# MAIN.net
KiCad netlist of a schematic drawn in Altium Designer
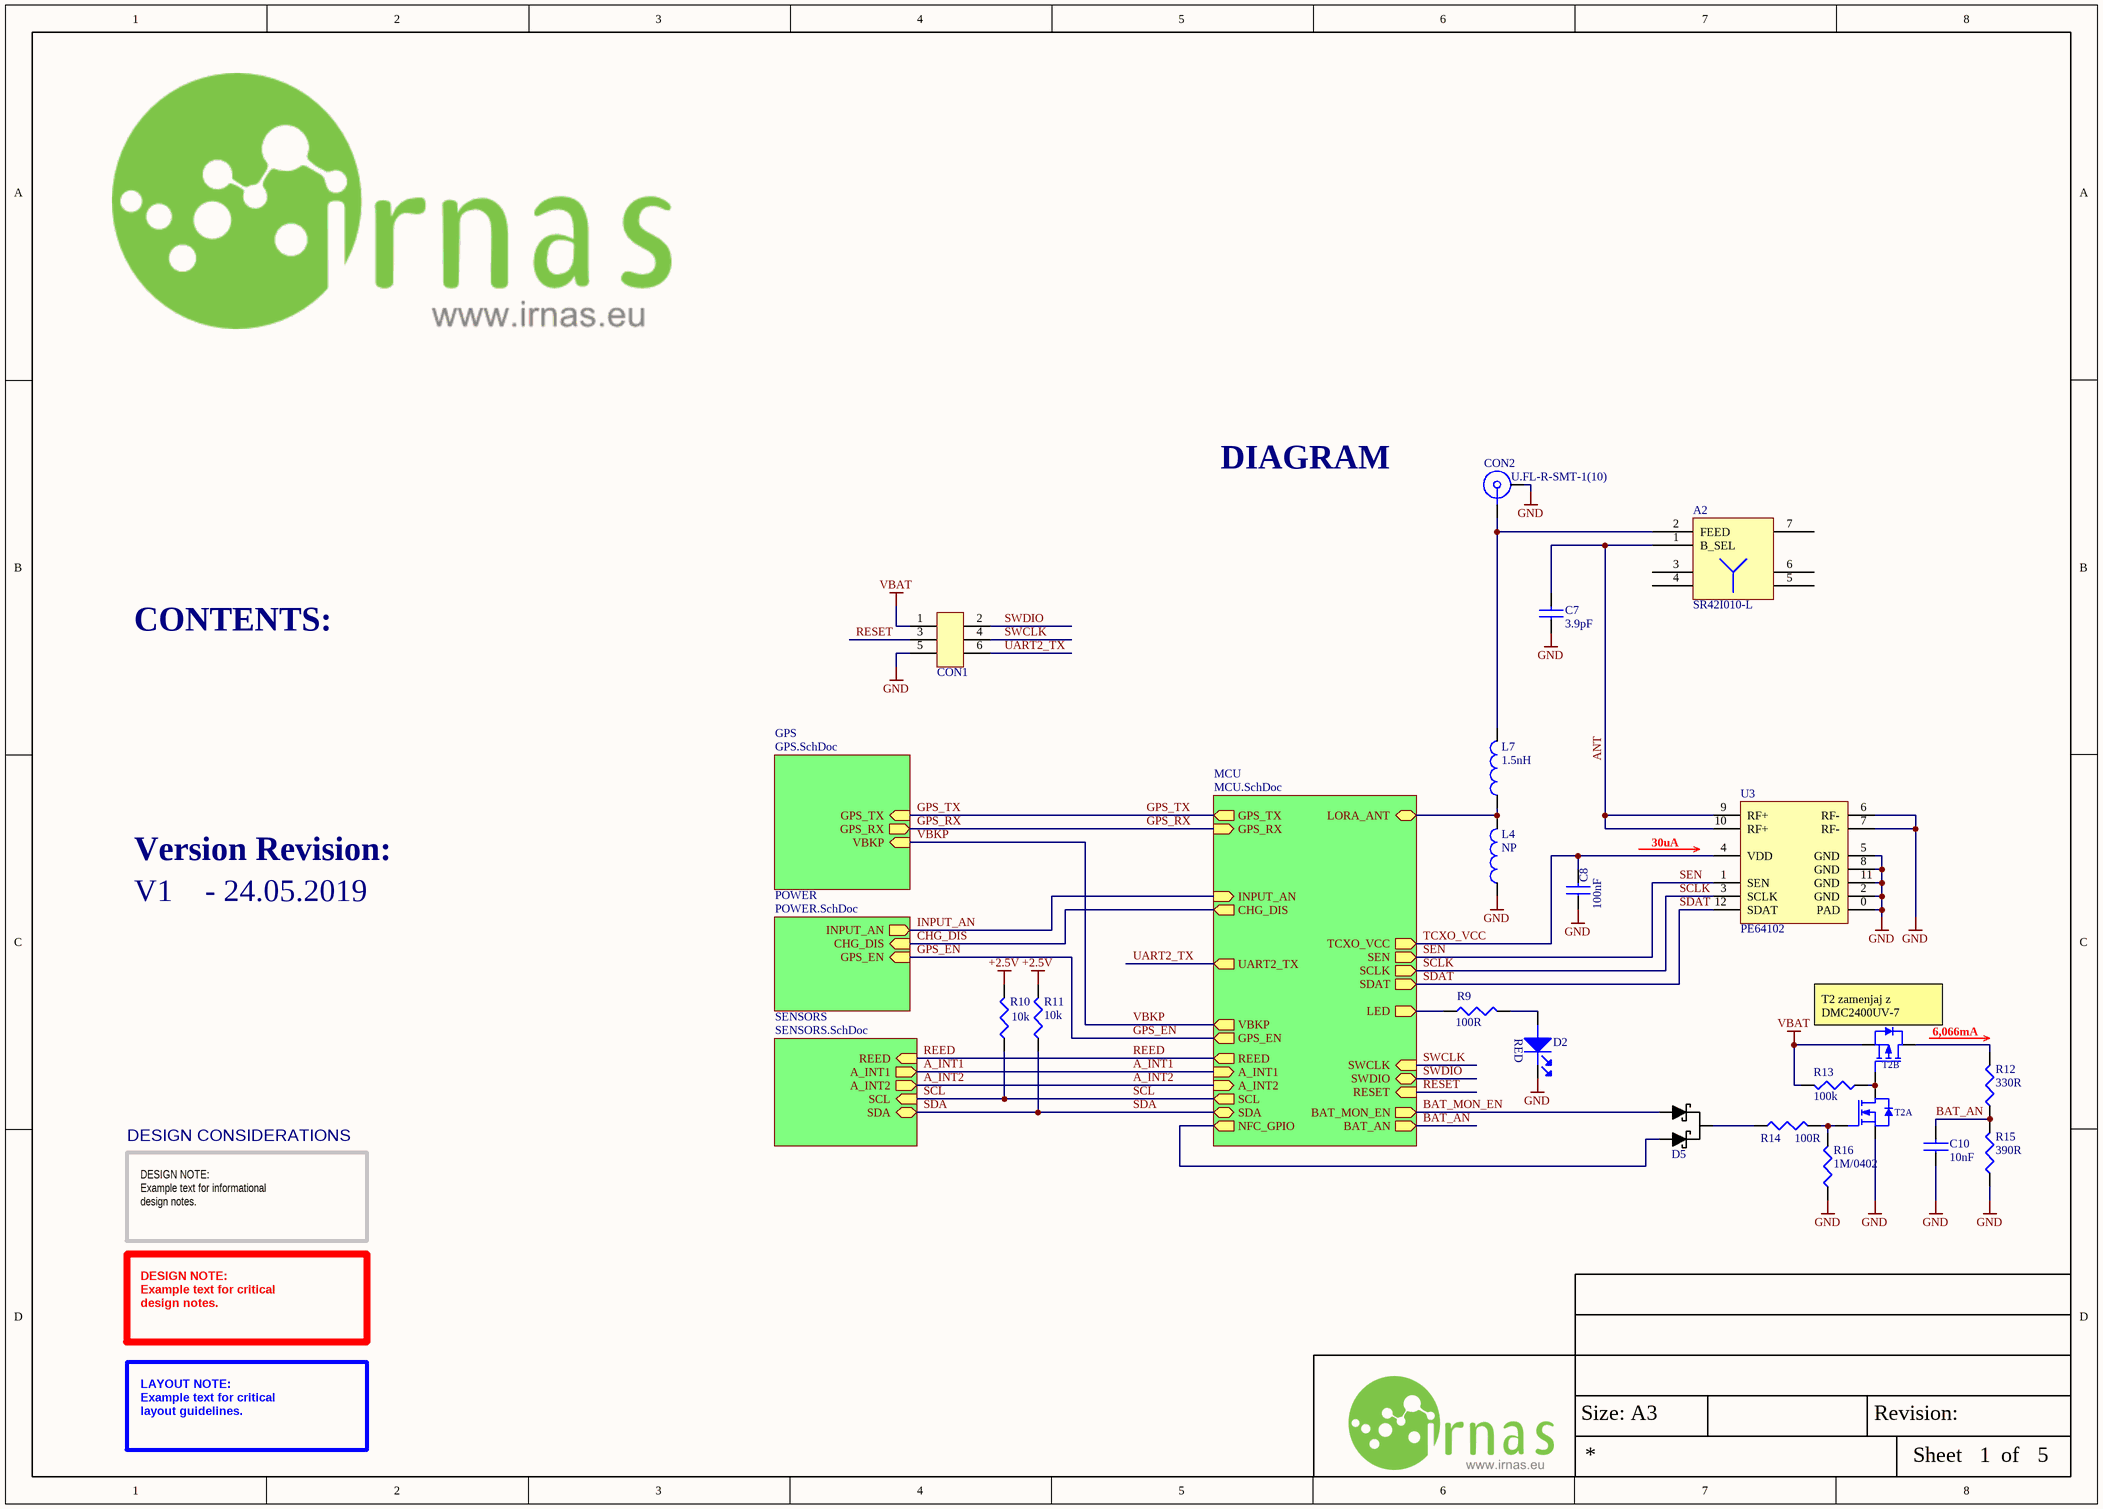
[diagram p0: MAIN.SchDoc]

(export (version "E")
  (design (tool "Eeschema 10.0.6"))
  (components
    (comp (ref "A2")
      (value "SR42I010-L")
      (footprint "SR42I010-L")
      (description "Antenna SMD -4dBi Gain 870MHz/928MHz Automotive 7-Pin SMD T/R")
      (fields (field (name "MANUFACTURER") "Antenova") (field (name "MANUFACTURER PART NUMBER") "SR42I010-R"))
      (libsource (lib "Passive") (part "ANT - SR42I010-L"))
    )
    (comp (ref "C7")
      (value "3.9pF")
      (footprint "CAP0402")
      (description "3.9 pF, 50 V, 0402 [1005 Metric], ± 0.25pF, NP0")
      (fields
        (field (name "MANUFACTURER") "KEMET")
        (field (name "MANUFACTURER PART NUMBER") "MC0402N3R9C500CT")
      )
      (libsource (lib "Passive") (part "C - 3.9pF/0402"))
    )
    (comp (ref "C8")
      (value "100nF")
      (footprint "CAP0402")
      (description "0.1 F, 16 V,  5%, X5R, MC Series")
      (fields
        (field (name "MANUFACTURER") "Multicomp")
        (field (name "MANUFACTURER PART NUMBER") "MC0402X104J160CT")
      )
      (libsource (lib "Passive") (part "C - 100nF/0402"))
    )
    (comp (ref "C10")
      (value "10nF")
      (footprint "CAP0402")
      (description "CAP CER 10000PF 16V X7R 0402")
      (fields
        (field (name "MANUFACTURER") "Murata")
        (field (name "MANUFACTURER PART NUMBER") "GRM155R71C103KA01D")
      )
      (libsource (lib "Passive") (part "C - 10nF/0402"))
    )
    (comp (ref "CON1")
      (value "Tag connect")
      (footprint "TC2030-IDC-NL")
      (libsource (lib "Connectors") (part "tag connecot 6 pin"))
    )
    (comp (ref "CON2")
      (value "U.FL-R-SMT-1(10)")
      (footprint "ufl connector smd")
      (description "RF / Coaxial Connector, U.FL Coaxial, Straight Jack, Surface Mount Vertical, 50 ohm, Brass")
      (fields (field (name "MANUFACTURER") "Hirose"))
      (libsource (lib "Connectors") (part "U.FL-R-SMT-1(10)"))
    )
    (comp (ref "D2")
      (value "LED RED")
      (footprint "LED0603")
      (description "BROADCOM LIMITED - HSMS-C190 - LED, RED, 10MCD, 626NM")
      (fields
        (field (name "MANUFACTURER") "BROADCOM LIMITED")
        (field (name "MANUFACTURER PART NUMBER") "HSMS-C190")
      )
      (libsource (lib "Active") (part "LED - LED RED"))
    )
    (comp (ref "D5")
      (value "BAS70-05,215")
      (footprint "SOT 23")
      (description "Small Signal Schottky Diode, Dual Common Cathode, 70 V, 70 mA, 410 mV, 100 mA, 150 °C")
      (libsource (lib "Active") (part "DS - BAS40-05"))
    )
    (comp (ref "L4")
      (value "NP")
      (footprint "IND0402")
      (description "Inductor RF Chip Multi-Layer 4.3nH 0.3nH 100MHz 8Q-Factor Air 300mA 210mOhm DCR 0402 Paper T/R")
      (fields
        (field (name "MANUFACTURER") "Murata")
        (field (name "MANUFACTURER PART NUMBER") "LQG15HN4N3S02D")
      )
      (libsource (lib "Passive") (part "L - 4.3nH/0402"))
    )
    (comp (ref "L7")
      (value "1.5nH")
      (footprint "IND0402")
      (description "1.5 nH, LQG15HS_02 Series, 1 A, 0402")
      (fields
        (field (name "MANUFACTURER") "Murata")
        (field (name "MANUFACTURER PART NUMBER") "LQG15HS1N5S02D")
      )
      (libsource (lib "Passive") (part "L - 1.5nH/0402"))
    )
    (comp (ref "R9")
      (value "100R")
      (footprint "RES0402")
      (description "100 ohm, 50 V, 0402 [1005 Metric], 62.5 mW,  1%")
      (fields
        (field (name "MANUFACTURER") "Multicomp")
        (field (name "MANUFACTURER PART NUMBER") "MCMR04X1000FTL")
      )
      (libsource (lib "Passive") (part "R - 100R/0402"))
    )
    (comp (ref "R10")
      (value "10k")
      (footprint "RES0402")
      (description "10 kohm, 50 V, 0402 [1005 Metric], 62.5 mW,  1%, MCWR Series")
      (fields
        (field (name "MANUFACTURER") "Multicomp")
        (field (name "MANUFACTURER PART NUMBER") "MCWR04X1002FTL")
      )
      (libsource (lib "Passive") (part "R - 10k/0402"))
    )
    (comp (ref "R11")
      (value "10k")
      (footprint "RES0402")
      (description "10 kohm, 50 V, 0402 [1005 Metric], 62.5 mW,  1%, MCWR Series")
      (fields
        (field (name "MANUFACTURER") "Multicomp")
        (field (name "MANUFACTURER PART NUMBER") "MCWR04X1002FTL")
      )
      (libsource (lib "Passive") (part "R - 10k/0402"))
    )
    (comp (ref "R12")
      (value "330R")
      (footprint "RES0402")
      (fields
        (field (name "MANUFACTURER") "Multicomp")
        (field (name "MANUFACTURER PART NUMBER") "MCMR04X3300FTL")
        (field (name "TOLERANCE") "1%")
      )
      (libsource (lib "Passive") (part "R - 330R/0402"))
    )
    (comp (ref "R13")
      (value "100k")
      (footprint "RES0402")
      (description "100KOHM, 1%, 0.0625W")
      (fields
        (field (name "MANUFACTURER") "Multicomp")
        (field (name "MANUFACTURER PART NUMBER") "MCWR04X1003FTL")
      )
      (libsource (lib "Passive") (part "R - 100k/0402"))
    )
    (comp (ref "R14")
      (value "100R")
      (footprint "RES0402")
      (description "100 ohm, 50 V, 0402 [1005 Metric], 62.5 mW,  1%")
      (fields
        (field (name "MANUFACTURER") "Multicomp")
        (field (name "MANUFACTURER PART NUMBER") "MCMR04X1000FTL")
      )
      (libsource (lib "Passive") (part "R - 100R/0402"))
    )
    (comp (ref "R15")
      (value "390R")
      (footprint "RES0402")
      (description "390 ohm, MCWR Series, 50 V, Thick Film, 62.5 mW")
      (fields (field (name "MANUFACTURER") "Multicomp") (field (name "MANUFACTURER PART NUMBER") "390/0402"))
      (libsource (lib "Passive") (part "R - 390R/0402"))
    )
    (comp (ref "R16")
      (value "1M/0402")
      (footprint "RES0402")
      (description "MCMR04X1004FTL RES, 1M, 1%, 0.0625W, 0402, THICK FILM")
      (fields
        (field (name "MANUFACTURER") "MULTICOMP")
        (field (name "MANUFACTURER PART NUMBER") "MC0063W060311M")
      )
      (libsource (lib "Passive") (part "R - 1M/0402"))
    )
    (comp (ref "T2")
      (value "VT6M1T2CR")
      (footprint "VMT6")
      (description "Dual MOSFET, N and P Channel, 100 mA, 20 V, 2.5 ohm, 4.5 V, 1 V")
      (fields (field (name "AUTHOR") "Ciril Golob"))
      (libsource (lib "Active") (part "T_M - VT6M1T2CR"))
    )
    (comp (ref "U3")
      (value "PE64102")
      (footprint "QFN-12")
      (description "RF IC Digitally Tunable Capacitor General Purpose 100MHz ~ 3GHz SPI Interface 12-QFN (2x2)")
      (fields (field (name "MANUFACTURER") "u-blox") (field (name "MANUFACTURER PART NUMBER") "MAX-M8Q-0"))
      (libsource (lib "Active") (part "RF - PE64102"))
    )
  )
  (nets
    (net (code "1") (name "+2.5V") (class "Default")
      (node (ref "R10") (pin "2") (pinfunction "2_2") (pintype "passive"))
      (node (ref "R11") (pin "2") (pinfunction "2_2") (pintype "passive"))
    )
    (net (code "2") (name "/ANT") (class "Default")
      (node (ref "A2") (pin "1") (pinfunction "B_SEL_1") (pintype "passive"))
      (node (ref "C7") (pin "2") (pinfunction "2_2") (pintype "passive"))
      (node (ref "U3") (pin "10") (pinfunction "RF+_10") (pintype "passive"))
      (node (ref "U3") (pin "9") (pinfunction "RF+_9") (pintype "passive"))
    )
    (net (code "5") (name "/BAT_AN") (class "Default")
      (node (ref "C10") (pin "2") (pinfunction "2_2") (pintype "passive"))
      (node (ref "R12") (pin "1") (pinfunction "1_1") (pintype "passive"))
      (node (ref "R15") (pin "2") (pinfunction "2_2") (pintype "passive"))
    )
    (net (code "6") (name "/BAT_MON_EN") (class "Default")
      (node (ref "D5") (pin "1") (pinfunction "ANODE_1") (pintype "passive"))
    )
    (net (code "12") (name "/LED") (class "Default")
      (node (ref "R9") (pin "1") (pinfunction "1_1") (pintype "passive"))
    )
    (net (code "13") (name "/LORA_ANT") (class "Default")
      (node (ref "L4") (pin "2") (pinfunction "2_2") (pintype "passive"))
      (node (ref "L7") (pin "1") (pinfunction "1_1") (pintype "passive"))
    )
    (net (code "14") (name "/NFC_GPIO") (class "Default")
      (node (ref "D5") (pin "2") (pinfunction "ANODE_2") (pintype "passive"))
    )
    (net (code "16") (name "/RESET") (class "Default")
      (node (ref "CON1") (pin "3") (pinfunction "3_3") (pintype "open_collector"))
    )
    (net (code "17") (name "/SCL") (class "Default")
      (node (ref "R10") (pin "1") (pinfunction "1_1") (pintype "passive"))
    )
    (net (code "18") (name "/SCLK") (class "Default")
      (node (ref "U3") (pin "3") (pinfunction "SCLK_3") (pintype "passive"))
    )
    (net (code "19") (name "/SDA") (class "Default")
      (node (ref "R11") (pin "1") (pinfunction "1_1") (pintype "passive"))
    )
    (net (code "20") (name "/SDAT") (class "Default")
      (node (ref "U3") (pin "12") (pinfunction "SDAT_12") (pintype "passive"))
    )
    (net (code "21") (name "/SEN") (class "Default")
      (node (ref "U3") (pin "1") (pinfunction "SEN_1") (pintype "passive"))
    )
    (net (code "22") (name "/SWCLK") (class "Default")
      (node (ref "CON1") (pin "4") (pinfunction "4_4") (pintype "open_collector"))
    )
    (net (code "23") (name "/SWDIO") (class "Default")
      (node (ref "CON1") (pin "2") (pinfunction "2_2") (pintype "open_collector"))
    )
    (net (code "24") (name "/TCXO_VCC") (class "Default")
      (node (ref "C8") (pin "2") (pinfunction "2_2") (pintype "passive"))
      (node (ref "U3") (pin "4") (pinfunction "VDD_4") (pintype "passive"))
    )
    (net (code "25") (name "/UART2_TX") (class "Default")
      (node (ref "CON1") (pin "6") (pinfunction "6_6") (pintype "passive"))
    )
    (net (code "27") (name "GND") (class "Default")
      (node (ref "C10") (pin "1") (pinfunction "1_1") (pintype "passive"))
      (node (ref "C7") (pin "1") (pinfunction "1_1") (pintype "passive"))
      (node (ref "C8") (pin "1") (pinfunction "1_1") (pintype "passive"))
      (node (ref "CON1") (pin "5") (pinfunction "5_5") (pintype "open_collector"))
      (node (ref "CON2") (pin "2") (pinfunction "2_2") (pintype "open_collector"))
      (node (ref "D2") (pin "1") (pinfunction "cathode_1") (pintype "passive"))
      (node (ref "L4") (pin "1") (pinfunction "1_1") (pintype "passive"))
      (node (ref "R15") (pin "1") (pinfunction "1_1") (pintype "passive"))
      (node (ref "R16") (pin "1") (pinfunction "1_1") (pintype "passive"))
      (node (ref "T2") (pin "1") (pinfunction "S1_1") (pintype "passive"))
      (node (ref "U3") (pin "0") (pinfunction "PAD_0") (pintype "passive"))
      (node (ref "U3") (pin "11") (pinfunction "GND_11") (pintype "passive"))
      (node (ref "U3") (pin "2") (pinfunction "GND_2") (pintype "passive"))
      (node (ref "U3") (pin "5") (pinfunction "GND_5") (pintype "passive"))
      (node (ref "U3") (pin "6") (pinfunction "RF-_6") (pintype "passive"))
      (node (ref "U3") (pin "7") (pinfunction "RF-_7") (pintype "passive"))
      (node (ref "U3") (pin "8") (pinfunction "GND_8") (pintype "passive"))
    )
    (net (code "28") (name "Net-(A2-FEED)") (class "Default")
      (node (ref "A2") (pin "2") (pinfunction "FEED_2") (pintype "passive"))
      (node (ref "CON2") (pin "1") (pinfunction "1_1") (pintype "open_collector"))
      (node (ref "L7") (pin "2") (pinfunction "2_2") (pintype "passive"))
    )
    (net (code "29") (name "Net-(D2-ANODE)") (class "Default")
      (node (ref "D2") (pin "2") (pinfunction "ANODE_2") (pintype "passive"))
      (node (ref "R9") (pin "2") (pinfunction "2_2") (pintype "passive"))
    )
    (net (code "30") (name "Net-(D5-C-A)") (class "Default")
      (node (ref "D5") (pin "3") (pinfunction "C-A_3") (pintype "passive"))
      (node (ref "R14") (pin "1") (pinfunction "1_1") (pintype "passive"))
    )
    (net (code "31") (name "Net-(T2A-D1)") (class "Default")
      (node (ref "R13") (pin "1") (pinfunction "1_1") (pintype "passive"))
      (node (ref "T2") (pin "5") (pinfunction "G2_5") (pintype "passive"))
      (node (ref "T2") (pin "6") (pinfunction "D1_6") (pintype "passive"))
    )
    (net (code "32") (name "Net-(T2A-G1)") (class "Default")
      (node (ref "R14") (pin "2") (pinfunction "2_2") (pintype "passive"))
      (node (ref "R16") (pin "2") (pinfunction "2_2") (pintype "passive"))
      (node (ref "T2") (pin "2") (pinfunction "G1_2") (pintype "passive"))
    )
    (net (code "33") (name "Net-(T2B-D2)") (class "Default")
      (node (ref "R12") (pin "2") (pinfunction "2_2") (pintype "passive"))
      (node (ref "T2") (pin "3") (pinfunction "D2_3") (pintype "passive"))
    )
    (net (code "34") (name "VBAT") (class "Default")
      (node (ref "CON1") (pin "1") (pinfunction "1_1") (pintype "open_collector"))
      (node (ref "R13") (pin "2") (pinfunction "2_2") (pintype "passive"))
      (node (ref "T2") (pin "4") (pinfunction "S2_4") (pintype "passive"))
    )
    (net (code "35") (name "unconnected-(A2-Pad3)") (class "Default")
      (node (ref "A2") (pin "3") (pintype "passive"))
    )
    (net (code "36") (name "unconnected-(A2-Pad4)") (class "Default")
      (node (ref "A2") (pin "4") (pintype "passive"))
    )
    (net (code "37") (name "unconnected-(A2-Pad5)") (class "Default")
      (node (ref "A2") (pin "5") (pintype "passive"))
    )
    (net (code "38") (name "unconnected-(A2-Pad6)") (class "Default")
      (node (ref "A2") (pin "6") (pintype "passive"))
    )
    (net (code "39") (name "unconnected-(A2-Pad7)") (class "Default")
      (node (ref "A2") (pin "7") (pintype "passive"))
    )
  )
)
